# OpenSnake.net
KiCad netlist of a schematic drawn in EAGLE
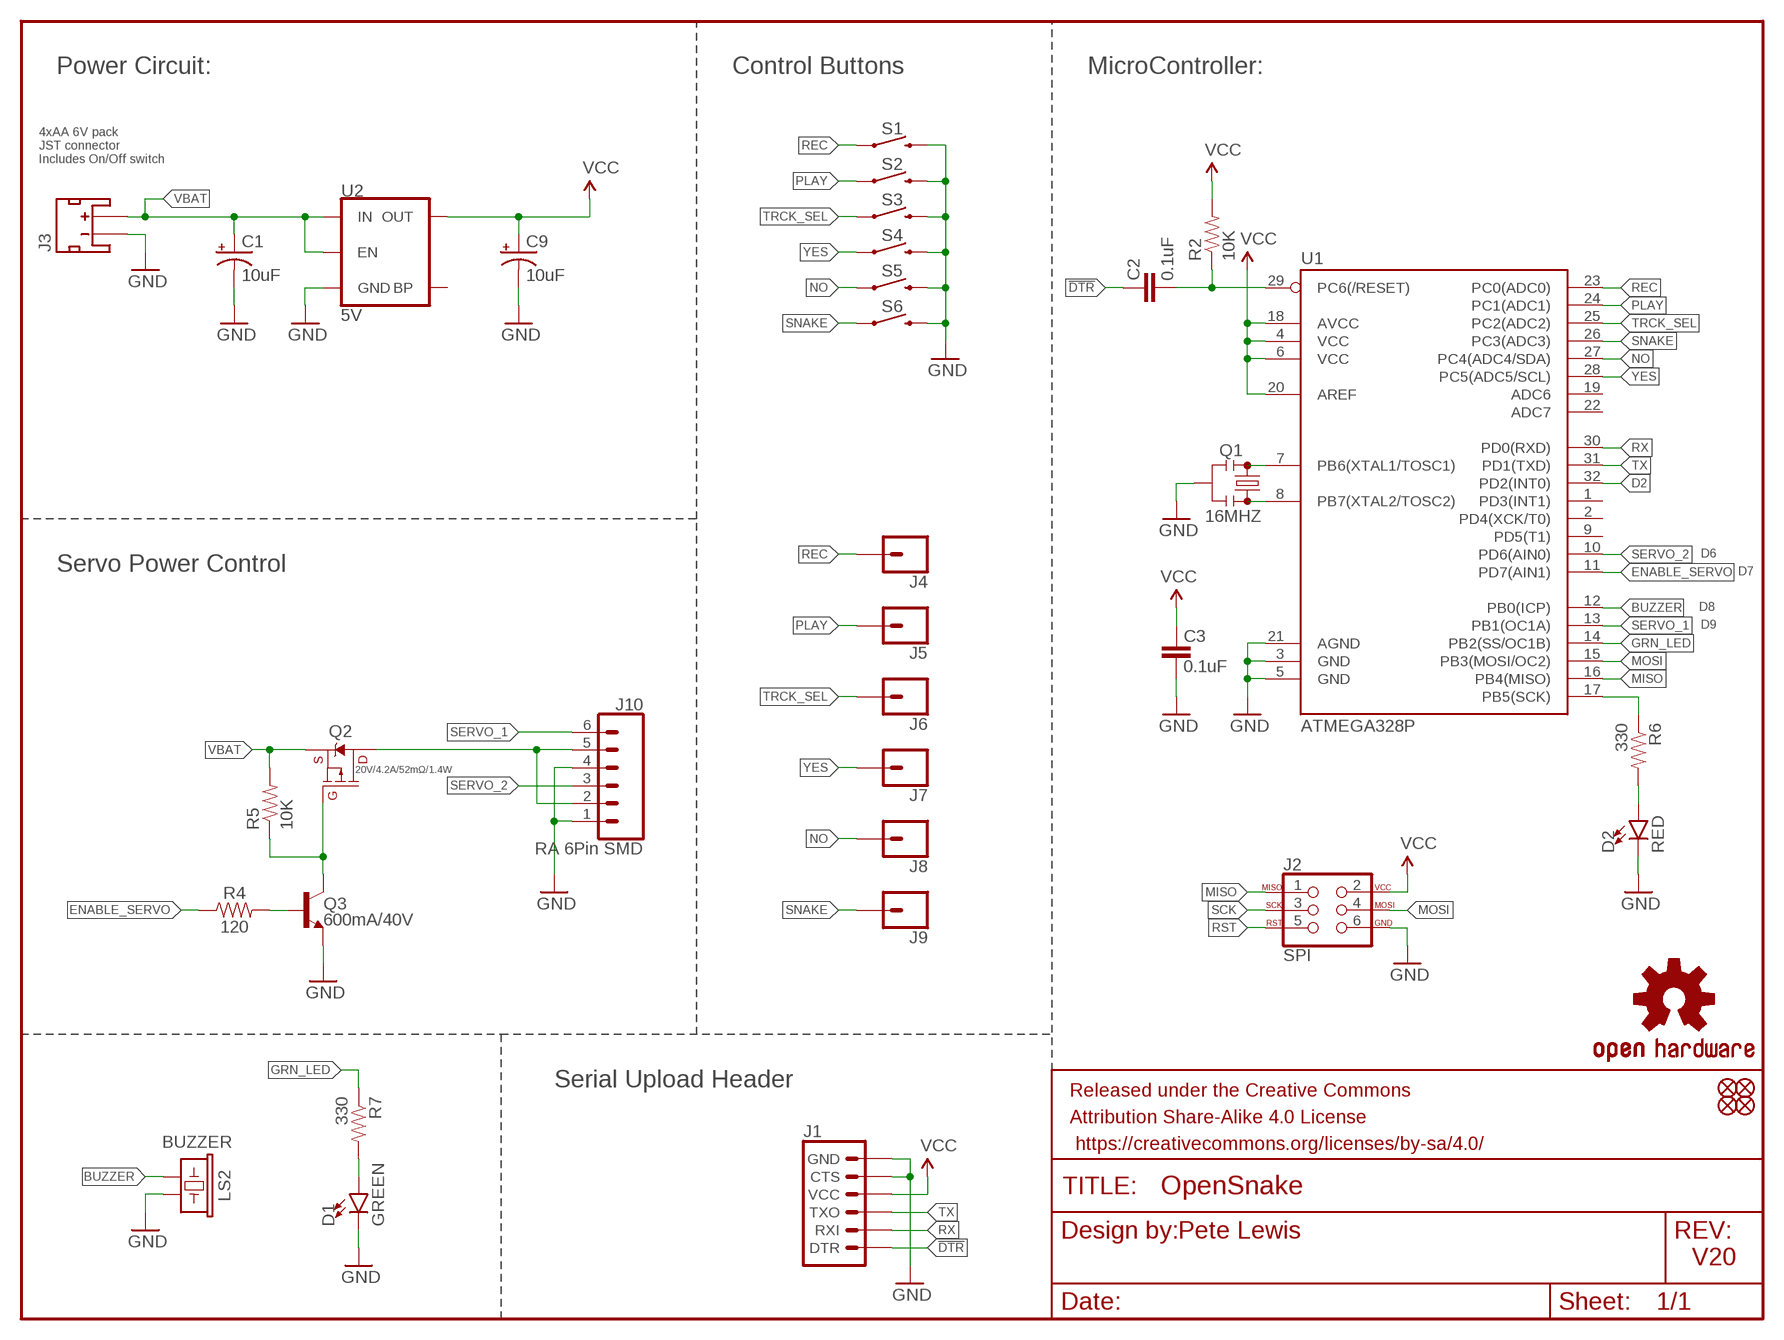
[diagram p0: schematic, sheet 1]

(export (version "E")
  (design (tool "Eeschema 10.0.6"))
  (components
    (comp (ref "C1")
      (value "10uF")
      (footprint "eagle-import:EIA3216")
      (libsource (lib "eagle-import") (part "10UF-POLAR-EIA3216-16V-10%(TANT)"))
    )
    (comp (ref "C2")
      (value "0.1uF")
      (footprint "eagle-import:0603-CAP")
      (libsource (lib "eagle-import") (part "0.1UF-25V(+80/-20%)(0603)"))
    )
    (comp (ref "C3")
      (value "0.1uF")
      (footprint "eagle-import:0603-CAP")
      (libsource (lib "eagle-import") (part "0.1UF-25V(+80/-20%)(0603)"))
    )
    (comp (ref "C9")
      (value "10uF")
      (footprint "eagle-import:EIA3216")
      (libsource (lib "eagle-import") (part "10UF-POLAR-EIA3216-16V-10%(TANT)"))
    )
    (comp (ref "D1")
      (value "GREEN")
      (footprint "eagle-import:LED-1206")
      (libsource (lib "eagle-import") (part "LED-GREEN1206"))
    )
    (comp (ref "D2")
      (value "RED")
      (footprint "eagle-import:LED-1206")
      (libsource (lib "eagle-import") (part "LED-RED1206"))
    )
    (comp (ref "FD1")
      (value "FIDUCIALUFIDUCIAL")
      (footprint "eagle-import:FIDUCIAL-MICRO")
      (libsource (lib "eagle-import") (part "FIDUCIALUFIDUCIAL"))
    )
    (comp (ref "FD2")
      (value "FIDUCIALUFIDUCIAL")
      (footprint "eagle-import:FIDUCIAL-MICRO")
      (libsource (lib "eagle-import") (part "FIDUCIALUFIDUCIAL"))
    )
    (comp (ref "FD3")
      (value "FIDUCIALUFIDUCIAL")
      (footprint "eagle-import:FIDUCIAL-MICRO")
      (libsource (lib "eagle-import") (part "FIDUCIALUFIDUCIAL"))
    )
    (comp (ref "FD4")
      (value "FIDUCIALUFIDUCIAL")
      (footprint "eagle-import:FIDUCIAL-MICRO")
      (libsource (lib "eagle-import") (part "FIDUCIALUFIDUCIAL"))
    )
    (comp (ref "FRAME1")
      (value "FRAME-LETTER")
      (footprint "eagle-import:CREATIVE_COMMONS")
      (libsource (lib "eagle-import") (part "FRAME-LETTER"))
    )
    (comp (ref "J1")
      (value "6_PIN_SERIAL_TARGETSILK")
      (footprint "eagle-import:6_PIN_SERIAL_TARGET_SIDE_W_SILK")
      (libsource (lib "eagle-import") (part "6_PIN_SERIAL_TARGETSILK"))
    )
    (comp (ref "J2")
      (value "SPI")
      (footprint "eagle-import:2X3_TEST_POINTS")
      (libsource (lib "eagle-import") (part "AVR_SPI_PROG_3X2TESTPOINTS"))
    )
    (comp (ref "J3")
      (value "JST_2MM_MALE")
      (footprint "eagle-import:JST-2-SMD")
      (libsource (lib "eagle-import") (part "JST_2MM_MALE"))
    )
    (comp (ref "J4")
      (value "CONN_01PTH_NO_SILK_YES_STOP")
      (footprint "eagle-import:1X01_NO_SILK")
      (libsource (lib "eagle-import") (part "CONN_01PTH_NO_SILK_YES_STOP"))
    )
    (comp (ref "J5")
      (value "CONN_01PTH_NO_SILK_YES_STOP")
      (footprint "eagle-import:1X01_NO_SILK")
      (libsource (lib "eagle-import") (part "CONN_01PTH_NO_SILK_YES_STOP"))
    )
    (comp (ref "J6")
      (value "CONN_01PTH_NO_SILK_YES_STOP")
      (footprint "eagle-import:1X01_NO_SILK")
      (libsource (lib "eagle-import") (part "CONN_01PTH_NO_SILK_YES_STOP"))
    )
    (comp (ref "J7")
      (value "CONN_01PTH_NO_SILK_YES_STOP")
      (footprint "eagle-import:1X01_NO_SILK")
      (libsource (lib "eagle-import") (part "CONN_01PTH_NO_SILK_YES_STOP"))
    )
    (comp (ref "J8")
      (value "CONN_01PTH_NO_SILK_YES_STOP")
      (footprint "eagle-import:1X01_NO_SILK")
      (libsource (lib "eagle-import") (part "CONN_01PTH_NO_SILK_YES_STOP"))
    )
    (comp (ref "J9")
      (value "CONN_01PTH_NO_SILK_YES_STOP")
      (footprint "eagle-import:1X01_NO_SILK")
      (libsource (lib "eagle-import") (part "CONN_01PTH_NO_SILK_YES_STOP"))
    )
    (comp (ref "J10")
      (value "RA 6Pin SMD")
      (footprint "eagle-import:1X06-SMD_RA_MALE")
      (libsource (lib "eagle-import") (part "CONN_06SMD"))
    )
    (comp (ref "LOGO1")
      (value "OSHW-LOGOL")
      (footprint "eagle-import:OSHW-LOGO-L")
      (libsource (lib "eagle-import") (part "OSHW-LOGOL"))
    )
    (comp (ref "LS2")
      (value "BUZZER")
      (footprint "eagle-import:BUZZER-CCV")
      (libsource (lib "eagle-import") (part "BUZZER-SMD"))
    )
    (comp (ref "Q1")
      (value "16MHZ")
      (footprint "eagle-import:RESONATOR-SMD")
      (libsource (lib "eagle-import") (part "RESONATOR16MHZ"))
    )
    (comp (ref "Q2")
      (value "20V/4.2A/52mΩ/1.4W")
      (footprint "eagle-import:SOT23-3")
      (libsource (lib "eagle-import") (part "MOSFET_PCH-DMG2305UX-7"))
    )
    (comp (ref "Q3")
      (value "600mA/40V")
      (footprint "eagle-import:SOT23-3")
      (libsource (lib "eagle-import") (part "TRANS_NPN-MMBT2222AL"))
    )
    (comp (ref "R2")
      (value "10K")
      (footprint "eagle-import:0603-RES")
      (libsource (lib "eagle-import") (part "10KOHM-1/10W-1%(0603)0603"))
    )
    (comp (ref "R4")
      (value "120")
      (footprint "eagle-import:0603")
      (libsource (lib "eagle-import") (part "100OHM-0603-1/10W-1%"))
    )
    (comp (ref "R5")
      (value "10K")
      (footprint "eagle-import:0603-RES")
      (libsource (lib "eagle-import") (part "10KOHM-1/10W-1%(0603)0603"))
    )
    (comp (ref "R6")
      (value "330")
      (footprint "eagle-import:0603-RES")
      (libsource (lib "eagle-import") (part "330OHM1/10W1%(0603)"))
    )
    (comp (ref "R7")
      (value "330")
      (footprint "eagle-import:0603-RES")
      (libsource (lib "eagle-import") (part "330OHM1/10W1%(0603)"))
    )
    (comp (ref "S1")
      (value "MOMENTARY-SWITCH-SPST-SMD-5.2MM-TALL")
      (footprint "eagle-import:TACTILE_SWITCH_SMD_5.2MM")
      (libsource (lib "eagle-import") (part "MOMENTARY-SWITCH-SPST-SMD-5.2MM-TALL"))
    )
    (comp (ref "S2")
      (value "MOMENTARY-SWITCH-SPST-SMD-5.2MM-TALL")
      (footprint "eagle-import:TACTILE_SWITCH_SMD_5.2MM")
      (libsource (lib "eagle-import") (part "MOMENTARY-SWITCH-SPST-SMD-5.2MM-TALL"))
    )
    (comp (ref "S3")
      (value "MOMENTARY-SWITCH-SPST-SMD-5.2MM-TALL")
      (footprint "eagle-import:TACTILE_SWITCH_SMD_5.2MM")
      (libsource (lib "eagle-import") (part "MOMENTARY-SWITCH-SPST-SMD-5.2MM-TALL"))
    )
    (comp (ref "S4")
      (value "MOMENTARY-SWITCH-SPST-SMD-5.2MM-TALL")
      (footprint "eagle-import:TACTILE_SWITCH_SMD_5.2MM")
      (libsource (lib "eagle-import") (part "MOMENTARY-SWITCH-SPST-SMD-5.2MM-TALL"))
    )
    (comp (ref "S5")
      (value "MOMENTARY-SWITCH-SPST-SMD-5.2MM-TALL")
      (footprint "eagle-import:TACTILE_SWITCH_SMD_5.2MM")
      (libsource (lib "eagle-import") (part "MOMENTARY-SWITCH-SPST-SMD-5.2MM-TALL"))
    )
    (comp (ref "S6")
      (value "MOMENTARY-SWITCH-SPST-SMD-5.2MM-TALL")
      (footprint "eagle-import:TACTILE_SWITCH_SMD_5.2MM")
      (libsource (lib "eagle-import") (part "MOMENTARY-SWITCH-SPST-SMD-5.2MM-TALL"))
    )
    (comp (ref "U1")
      (value "ATMEGA328P")
      (footprint "eagle-import:TQFP32-08")
      (libsource (lib "eagle-import") (part "ATMEGA328P_TQFP"))
    )
    (comp (ref "U2")
      (value "5V")
      (footprint "eagle-import:SOT23-5")
      (libsource (lib "eagle-import") (part "V_REG_MIC52055V"))
    )
  )
  (nets
    (net (code "1") (name "/~{DTR}") (class "Default")
      (node (ref "C2") (pin "2") (pinfunction "2_2") (pintype "passive"))
      (node (ref "J1") (pin "P$1") (pinfunction "DTR_P$1") (pintype "passive"))
    )
    (net (code "2") (name "BUZZER") (class "Default")
      (node (ref "LS2") (pin "-") (pinfunction "2_-") (pintype "passive"))
      (node (ref "U1") (pin "12") (pinfunction "PB0(ICP)_12") (pintype "bidirectional"))
    )
    (net (code "3") (name "D2") (class "Default")
      (node (ref "U1") (pin "32") (pinfunction "PD2(INT0)_32") (pintype "bidirectional"))
    )
    (net (code "4") (name "ENABLE_SERVO") (class "Default")
      (node (ref "R4") (pin "1") (pinfunction "1_1") (pintype "passive"))
      (node (ref "U1") (pin "11") (pinfunction "PD7(AIN1)_11") (pintype "bidirectional"))
    )
    (net (code "5") (name "GND") (class "Default")
      (node (ref "C1") (pin "-") (pinfunction "-_-") (pintype "passive"))
      (node (ref "C3") (pin "1") (pinfunction "1_1") (pintype "passive"))
      (node (ref "C9") (pin "-") (pinfunction "-_-") (pintype "passive"))
      (node (ref "D1") (pin "C") (pinfunction "C_C") (pintype "passive"))
      (node (ref "D2") (pin "C") (pinfunction "C_C") (pintype "passive"))
      (node (ref "J1") (pin "P$5") (pinfunction "CTS_P$5") (pintype "passive"))
      (node (ref "J1") (pin "P$6") (pinfunction "GND_P$6") (pintype "passive"))
      (node (ref "J10") (pin "1") (pinfunction "1_1") (pintype "passive"))
      (node (ref "J10") (pin "4") (pinfunction "4_4") (pintype "passive"))
      (node (ref "J2") (pin "6") (pinfunction "6_6") (pintype "passive"))
      (node (ref "J3") (pin "1") (pinfunction "-_1") (pintype "bidirectional"))
      (node (ref "LS2") (pin "+") (pinfunction "1_+") (pintype "passive"))
      (node (ref "Q1") (pin "2") (pinfunction "2_2") (pintype "passive"))
      (node (ref "Q3") (pin "2") (pinfunction "E_2") (pintype "passive"))
      (node (ref "S1") (pin "3") (pinfunction "2_3") (pintype "passive"))
      (node (ref "S2") (pin "3") (pinfunction "2_3") (pintype "passive"))
      (node (ref "S3") (pin "3") (pinfunction "2_3") (pintype "passive"))
      (node (ref "S4") (pin "3") (pinfunction "2_3") (pintype "passive"))
      (node (ref "S5") (pin "3") (pinfunction "2_3") (pintype "passive"))
      (node (ref "S6") (pin "3") (pinfunction "2_3") (pintype "passive"))
      (node (ref "U1") (pin "21") (pinfunction "AGND_21") (pintype "bidirectional"))
      (node (ref "U1") (pin "3") (pinfunction "GND_3") (pintype "bidirectional"))
      (node (ref "U1") (pin "5") (pinfunction "GND_5") (pintype "bidirectional"))
      (node (ref "U2") (pin "2") (pinfunction "GND_2") (pintype "input"))
    )
    (net (code "6") (name "GRN_LED") (class "Default")
      (node (ref "R7") (pin "1") (pinfunction "1_1") (pintype "passive"))
      (node (ref "U1") (pin "14") (pinfunction "PB2(SS/OC1B)_14") (pintype "bidirectional"))
    )
    (net (code "7") (name "MISO") (class "Default")
      (node (ref "J2") (pin "1") (pinfunction "1_1") (pintype "passive"))
      (node (ref "U1") (pin "16") (pinfunction "PB4(MISO)_16") (pintype "bidirectional"))
    )
    (net (code "8") (name "MOSI") (class "Default")
      (node (ref "J2") (pin "4") (pinfunction "4_4") (pintype "passive"))
      (node (ref "U1") (pin "15") (pinfunction "PB3(MOSI/OC2)_15") (pintype "bidirectional"))
    )
    (net (code "9") (name "NO") (class "Default")
      (node (ref "J8") (pin "1") (pinfunction "1_1") (pintype "passive"))
      (node (ref "S5") (pin "1") (pinfunction "1_1") (pintype "passive"))
      (node (ref "U1") (pin "27") (pinfunction "PC4(ADC4/SDA)_27") (pintype "bidirectional"))
    )
    (net (code "10") (name "Net-(D1-PadA)") (class "Default")
      (node (ref "D1") (pin "A") (pinfunction "A_A") (pintype "passive"))
      (node (ref "R7") (pin "2") (pinfunction "2_2") (pintype "passive"))
    )
    (net (code "11") (name "Net-(D2-PadA)") (class "Default")
      (node (ref "D2") (pin "A") (pinfunction "A_A") (pintype "passive"))
      (node (ref "R6") (pin "2") (pinfunction "2_2") (pintype "passive"))
    )
    (net (code "12") (name "Net-(Q2-D)") (class "Default")
      (node (ref "J10") (pin "2") (pinfunction "2_2") (pintype "passive"))
      (node (ref "J10") (pin "5") (pinfunction "5_5") (pintype "passive"))
      (node (ref "Q2") (pin "3") (pinfunction "D_3") (pintype "bidirectional"))
    )
    (net (code "13") (name "Net-(Q2-G)") (class "Default")
      (node (ref "Q2") (pin "1") (pinfunction "G_1") (pintype "bidirectional"))
      (node (ref "Q3") (pin "3") (pinfunction "C_3") (pintype "passive"))
      (node (ref "R5") (pin "1") (pinfunction "1_1") (pintype "passive"))
    )
    (net (code "14") (name "Net-(Q3-B)") (class "Default")
      (node (ref "Q3") (pin "1") (pinfunction "B_1") (pintype "passive"))
      (node (ref "R4") (pin "2") (pinfunction "2_2") (pintype "passive"))
    )
    (net (code "15") (name "Net-(U1-PB6(XTAL1{slash}TOSC1))") (class "Default")
      (node (ref "Q1") (pin "3") (pinfunction "3_3") (pintype "passive"))
      (node (ref "U1") (pin "7") (pinfunction "PB6(XTAL1/TOSC1)_7") (pintype "bidirectional"))
    )
    (net (code "16") (name "Net-(U1-PB7(XTAL2{slash}TOSC2))") (class "Default")
      (node (ref "Q1") (pin "1") (pinfunction "1_1") (pintype "passive"))
      (node (ref "U1") (pin "8") (pinfunction "PB7(XTAL2/TOSC2)_8") (pintype "bidirectional"))
    )
    (net (code "17") (name "PLAY") (class "Default")
      (node (ref "J5") (pin "1") (pinfunction "1_1") (pintype "passive"))
      (node (ref "S2") (pin "1") (pinfunction "1_1") (pintype "passive"))
      (node (ref "U1") (pin "24") (pinfunction "PC1(ADC1)_24") (pintype "bidirectional"))
    )
    (net (code "18") (name "REC") (class "Default")
      (node (ref "J4") (pin "1") (pinfunction "1_1") (pintype "passive"))
      (node (ref "S1") (pin "1") (pinfunction "1_1") (pintype "passive"))
      (node (ref "U1") (pin "23") (pinfunction "PC0(ADC0)_23") (pintype "bidirectional"))
    )
    (net (code "19") (name "RST") (class "Default")
      (node (ref "C2") (pin "1") (pinfunction "1_1") (pintype "passive"))
      (node (ref "J2") (pin "5") (pinfunction "5_5") (pintype "passive"))
      (node (ref "R2") (pin "1") (pinfunction "1_1") (pintype "passive"))
      (node (ref "U1") (pin "29") (pinfunction "PC6(/RESET)_29") (pintype "bidirectional"))
    )
    (net (code "20") (name "RX") (class "Default")
      (node (ref "J1") (pin "P$3") (pinfunction "RXI_P$3") (pintype "passive"))
      (node (ref "U1") (pin "30") (pinfunction "PD0(RXD)_30") (pintype "bidirectional"))
    )
    (net (code "21") (name "SCK") (class "Default")
      (node (ref "J2") (pin "3") (pinfunction "3_3") (pintype "passive"))
      (node (ref "R6") (pin "1") (pinfunction "1_1") (pintype "passive"))
      (node (ref "U1") (pin "17") (pinfunction "PB5(SCK)_17") (pintype "bidirectional"))
    )
    (net (code "22") (name "SERVO_1") (class "Default")
      (node (ref "J10") (pin "6") (pinfunction "6_6") (pintype "passive"))
      (node (ref "U1") (pin "13") (pinfunction "PB1(OC1A)_13") (pintype "bidirectional"))
    )
    (net (code "23") (name "SERVO_2") (class "Default")
      (node (ref "J10") (pin "3") (pinfunction "3_3") (pintype "passive"))
      (node (ref "U1") (pin "10") (pinfunction "PD6(AIN0)_10") (pintype "bidirectional"))
    )
    (net (code "24") (name "SNAKE") (class "Default")
      (node (ref "J9") (pin "1") (pinfunction "1_1") (pintype "passive"))
      (node (ref "S6") (pin "1") (pinfunction "1_1") (pintype "passive"))
      (node (ref "U1") (pin "26") (pinfunction "PC3(ADC3)_26") (pintype "bidirectional"))
    )
    (net (code "25") (name "TRCK_SEL") (class "Default")
      (node (ref "J6") (pin "1") (pinfunction "1_1") (pintype "passive"))
      (node (ref "S3") (pin "1") (pinfunction "1_1") (pintype "passive"))
      (node (ref "U1") (pin "25") (pinfunction "PC2(ADC2)_25") (pintype "bidirectional"))
    )
    (net (code "26") (name "TX") (class "Default")
      (node (ref "J1") (pin "P$2") (pinfunction "TXO_P$2") (pintype "passive"))
      (node (ref "U1") (pin "31") (pinfunction "PD1(TXD)_31") (pintype "bidirectional"))
    )
    (net (code "27") (name "VBAT") (class "Default")
      (node (ref "C1") (pin "+") (pinfunction "+_+") (pintype "passive"))
      (node (ref "J3") (pin "2") (pinfunction "+_2") (pintype "bidirectional"))
      (node (ref "Q2") (pin "2") (pinfunction "S_2") (pintype "bidirectional"))
      (node (ref "R5") (pin "2") (pinfunction "2_2") (pintype "passive"))
      (node (ref "U2") (pin "1") (pinfunction "IN_1") (pintype "input"))
      (node (ref "U2") (pin "3") (pinfunction "EN_3") (pintype "input"))
    )
    (net (code "28") (name "VCC") (class "Default")
      (node (ref "C3") (pin "2") (pinfunction "2_2") (pintype "passive"))
      (node (ref "C9") (pin "+") (pinfunction "+_+") (pintype "passive"))
      (node (ref "J1") (pin "P$4") (pinfunction "VCC_P$4") (pintype "passive"))
      (node (ref "J2") (pin "2") (pinfunction "2_2") (pintype "passive"))
      (node (ref "R2") (pin "2") (pinfunction "2_2") (pintype "passive"))
      (node (ref "U1") (pin "18") (pinfunction "AVCC_18") (pintype "bidirectional"))
      (node (ref "U1") (pin "20") (pinfunction "AREF_20") (pintype "bidirectional"))
      (node (ref "U1") (pin "4") (pinfunction "VCC_4") (pintype "bidirectional"))
      (node (ref "U1") (pin "6") (pinfunction "VCC_6") (pintype "bidirectional"))
      (node (ref "U2") (pin "5") (pinfunction "OUT_5") (pintype "passive"))
    )
    (net (code "29") (name "YES") (class "Default")
      (node (ref "J7") (pin "1") (pinfunction "1_1") (pintype "passive"))
      (node (ref "S4") (pin "1") (pinfunction "1_1") (pintype "passive"))
      (node (ref "U1") (pin "28") (pinfunction "PC5(ADC5/SCL)_28") (pintype "bidirectional"))
    )
    (net (code "30") (name "unconnected-(J3-PAD1-PadNC1)") (class "Default")
      (node (ref "J3") (pin "NC1") (pinfunction "PAD1_NC1") (pintype "bidirectional"))
    )
    (net (code "31") (name "unconnected-(J3-PAD2-PadNC2)") (class "Default")
      (node (ref "J3") (pin "NC2") (pinfunction "PAD2_NC2") (pintype "bidirectional"))
    )
    (net (code "32") (name "unconnected-(U1-ADC6-Pad19)") (class "Default")
      (node (ref "U1") (pin "19") (pinfunction "ADC6_19") (pintype "bidirectional"))
    )
    (net (code "33") (name "unconnected-(U1-ADC7-Pad22)") (class "Default")
      (node (ref "U1") (pin "22") (pinfunction "ADC7_22") (pintype "bidirectional"))
    )
    (net (code "34") (name "unconnected-(U1-PD3(INT1)-Pad1)") (class "Default")
      (node (ref "U1") (pin "1") (pinfunction "PD3(INT1)_1") (pintype "bidirectional"))
    )
    (net (code "35") (name "unconnected-(U1-PD4(XCK{slash}T0)-Pad2)") (class "Default")
      (node (ref "U1") (pin "2") (pinfunction "PD4(XCK/T0)_2") (pintype "bidirectional"))
    )
    (net (code "36") (name "unconnected-(U1-PD5(T1)-Pad9)") (class "Default")
      (node (ref "U1") (pin "9") (pinfunction "PD5(T1)_9") (pintype "bidirectional"))
    )
    (net (code "37") (name "unconnected-(U2-BP-Pad4)") (class "Default")
      (node (ref "U2") (pin "4") (pinfunction "BP_4") (pintype "input"))
    )
  )
)
